# arduino_mini_can_bus.net
KiCad netlist of a schematic drawn in EAGLE
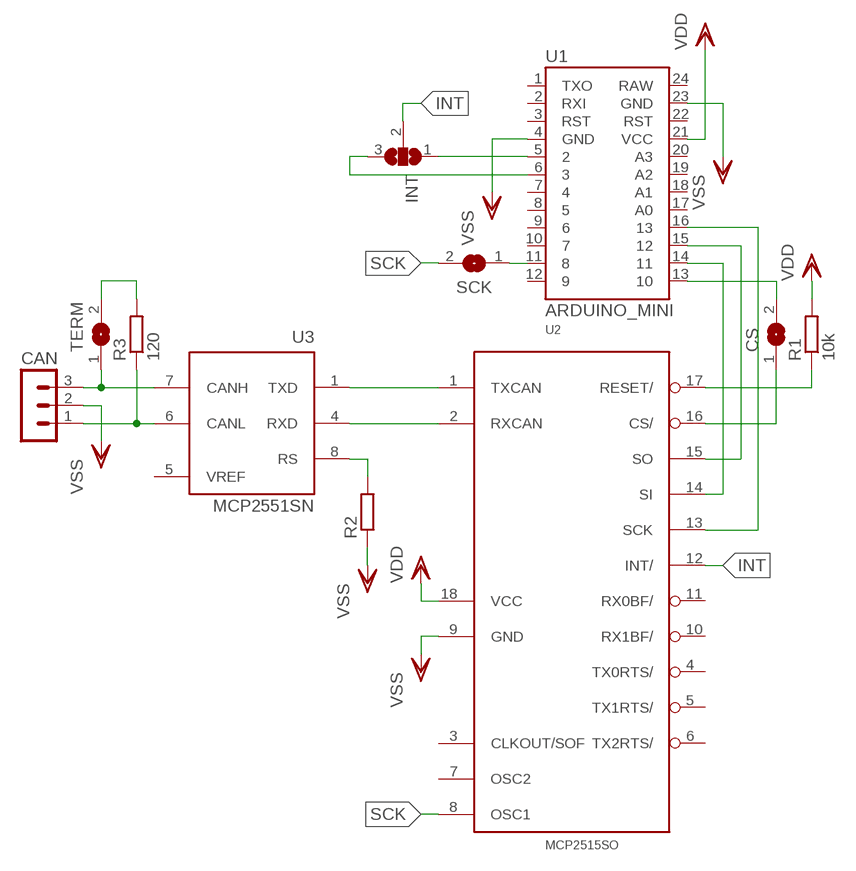
[diagram p0: schematic, sheet 1]

(export (version "E")
  (design (tool "Eeschema 10.0.6"))
  (components
    (comp (ref "CAN")
      (value "MA03-1")
      (footprint "eagle-import:MA03-1")
      (libsource (lib "eagle-import") (part "MA03-1"))
    )
    (comp (ref "CS") (value "SJ") (footprint "eagle-import:SJ") (libsource (lib "eagle-import") (part "SJ")))
    (comp (ref "INT")
      (value "SJ2W")
      (footprint "eagle-import:SJ_2")
      (libsource (lib "eagle-import") (part "SJ2W"))
    )
    (comp (ref "R1")
      (value "10k")
      (footprint "eagle-import:0207_10")
      (libsource (lib "eagle-import") (part "R-EU_0207/10"))
    )
    (comp (ref "R2")
      (value "R-EU_0207/10")
      (footprint "eagle-import:0207_10")
      (libsource (lib "eagle-import") (part "R-EU_0207/10"))
    )
    (comp (ref "R3")
      (value "120")
      (footprint "eagle-import:0207_10")
      (libsource (lib "eagle-import") (part "R-EU_0207/10"))
    )
    (comp (ref "SCK") (value "SJ") (footprint "eagle-import:SJ") (libsource (lib "eagle-import") (part "SJ")))
    (comp (ref "TERM")
      (value "SJ")
      (footprint "eagle-import:SJ")
      (libsource (lib "eagle-import") (part "SJ"))
    )
    (comp (ref "U1")
      (value "ARDUINO_MINI")
      (footprint "eagle-import:ARDUINO_MINI")
      (libsource (lib "eagle-import") (part "ARDUINO_MINI"))
    )
    (comp (ref "U2")
      (value "MCP2515SO")
      (footprint "eagle-import:SO18L")
      (libsource (lib "eagle-import") (part "MCP2515SO"))
    )
    (comp (ref "U3")
      (value "MCP2551SN")
      (footprint "eagle-import:SO-08")
      (libsource (lib "eagle-import") (part "MCP2551SN"))
    )
  )
  (nets
    (net (code "1") (name "/VREF") (class "Default")
      (node (ref "U3") (pin "5") (pinfunction "VREF_5") (pintype "power_in"))
    )
    (net (code "2") (name "INT") (class "Default")
      (node (ref "INT") (pin "2") (pinfunction "2_2") (pintype "passive"))
      (node (ref "U2") (pin "12") (pinfunction "INT/_12") (pintype "output"))
    )
    (net (code "3") (name "Net-(R3-Pad2)") (class "Default")
      (node (ref "R3") (pin "2") (pinfunction "2_2") (pintype "passive"))
      (node (ref "TERM") (pin "2") (pinfunction "2_2") (pintype "passive"))
    )
    (net (code "4") (name "Net-(U1-2)") (class "Default")
      (node (ref "INT") (pin "1") (pinfunction "1_1") (pintype "passive"))
      (node (ref "U1") (pin "5") (pinfunction "2_5") (pintype "bidirectional"))
    )
    (net (code "5") (name "Net-(U1-3)") (class "Default")
      (node (ref "INT") (pin "3") (pinfunction "3_3") (pintype "passive"))
      (node (ref "U1") (pin "6") (pinfunction "3_6") (pintype "bidirectional"))
    )
    (net (code "6") (name "Net-(U1-8)") (class "Default")
      (node (ref "SCK") (pin "1") (pinfunction "1_1") (pintype "passive"))
      (node (ref "U1") (pin "11") (pinfunction "8_11") (pintype "bidirectional"))
    )
    (net (code "7") (name "Net-(U1-10)") (class "Default")
      (node (ref "CS") (pin "2") (pinfunction "2_2") (pintype "passive"))
      (node (ref "U1") (pin "13") (pinfunction "10_13") (pintype "bidirectional"))
    )
    (net (code "8") (name "Net-(U1-11)") (class "Default")
      (node (ref "U1") (pin "14") (pinfunction "11_14") (pintype "bidirectional"))
      (node (ref "U2") (pin "14") (pinfunction "SI_14") (pintype "input"))
    )
    (net (code "9") (name "Net-(U1-12)") (class "Default")
      (node (ref "U1") (pin "15") (pinfunction "12_15") (pintype "bidirectional"))
      (node (ref "U2") (pin "15") (pinfunction "SO_15") (pintype "output"))
    )
    (net (code "10") (name "Net-(U1-13)") (class "Default")
      (node (ref "U1") (pin "16") (pinfunction "13_16") (pintype "bidirectional"))
      (node (ref "U2") (pin "13") (pinfunction "SCK_13") (pintype "input"))
    )
    (net (code "11") (name "Net-(U2-CS{slash})") (class "Default")
      (node (ref "CS") (pin "1") (pinfunction "1_1") (pintype "passive"))
      (node (ref "U2") (pin "16") (pinfunction "CS/_16") (pintype "input"))
    )
    (net (code "12") (name "Net-(U2-RESET{slash})") (class "Default")
      (node (ref "R1") (pin "1") (pinfunction "1_1") (pintype "passive"))
      (node (ref "U2") (pin "17") (pinfunction "RESET/_17") (pintype "input"))
    )
    (net (code "13") (name "Net-(U2-RXCAN)") (class "Default")
      (node (ref "U2") (pin "2") (pinfunction "RXCAN_2") (pintype "input"))
      (node (ref "U3") (pin "4") (pinfunction "RXD_4") (pintype "output"))
    )
    (net (code "14") (name "Net-(U2-TXCAN)") (class "Default")
      (node (ref "U2") (pin "1") (pinfunction "TXCAN_1") (pintype "output"))
      (node (ref "U3") (pin "1") (pinfunction "TXD_1") (pintype "input"))
    )
    (net (code "15") (name "Net-(U3A-CANH)") (class "Default")
      (node (ref "CAN") (pin "3") (pinfunction "3_3") (pintype "passive"))
      (node (ref "TERM") (pin "1") (pinfunction "1_1") (pintype "passive"))
      (node (ref "U3") (pin "7") (pinfunction "CANH_7") (pintype "bidirectional"))
    )
    (net (code "16") (name "Net-(U3A-CANL)") (class "Default")
      (node (ref "CAN") (pin "1") (pinfunction "1_1") (pintype "passive"))
      (node (ref "R3") (pin "1") (pinfunction "1_1") (pintype "passive"))
      (node (ref "U3") (pin "6") (pinfunction "CANL_6") (pintype "bidirectional"))
    )
    (net (code "17") (name "Net-(U3A-RS)") (class "Default")
      (node (ref "R2") (pin "2") (pinfunction "2_2") (pintype "passive"))
      (node (ref "U3") (pin "8") (pinfunction "RS_8") (pintype "input"))
    )
    (net (code "18") (name "SCK") (class "Default")
      (node (ref "SCK") (pin "2") (pinfunction "2_2") (pintype "passive"))
      (node (ref "U2") (pin "8") (pinfunction "OSC1_8") (pintype "bidirectional"))
    )
    (net (code "19") (name "VDD") (class "Default")
      (node (ref "R1") (pin "2") (pinfunction "2_2") (pintype "passive"))
      (node (ref "U1") (pin "21") (pinfunction "VCC_21") (pintype "bidirectional"))
      (node (ref "U2") (pin "18") (pinfunction "VCC_18") (pintype "power_in"))
    )
    (net (code "20") (name "VSS") (class "Default")
      (node (ref "CAN") (pin "2") (pinfunction "2_2") (pintype "passive"))
      (node (ref "R2") (pin "1") (pinfunction "1_1") (pintype "passive"))
      (node (ref "U1") (pin "23") (pinfunction "GND_23") (pintype "bidirectional"))
      (node (ref "U1") (pin "4") (pinfunction "GND_4") (pintype "bidirectional"))
      (node (ref "U2") (pin "9") (pinfunction "GND_9") (pintype "power_in"))
    )
    (net (code "21") (name "unconnected-(U1-4-Pad7)") (class "Default")
      (node (ref "U1") (pin "7") (pinfunction "4_7") (pintype "bidirectional"))
    )
    (net (code "22") (name "unconnected-(U1-5-Pad8)") (class "Default")
      (node (ref "U1") (pin "8") (pinfunction "5_8") (pintype "bidirectional"))
    )
    (net (code "23") (name "unconnected-(U1-6-Pad9)") (class "Default")
      (node (ref "U1") (pin "9") (pinfunction "6_9") (pintype "bidirectional"))
    )
    (net (code "24") (name "unconnected-(U1-7-Pad10)") (class "Default")
      (node (ref "U1") (pin "10") (pinfunction "7_10") (pintype "bidirectional"))
    )
    (net (code "25") (name "unconnected-(U1-9-Pad12)") (class "Default")
      (node (ref "U1") (pin "12") (pinfunction "9_12") (pintype "bidirectional"))
    )
    (net (code "26") (name "unconnected-(U1-A0-Pad17)") (class "Default")
      (node (ref "U1") (pin "17") (pinfunction "A0_17") (pintype "bidirectional"))
    )
    (net (code "27") (name "unconnected-(U1-A1-Pad18)") (class "Default")
      (node (ref "U1") (pin "18") (pinfunction "A1_18") (pintype "bidirectional"))
    )
    (net (code "28") (name "unconnected-(U1-A2-Pad19)") (class "Default")
      (node (ref "U1") (pin "19") (pinfunction "A2_19") (pintype "bidirectional"))
    )
    (net (code "29") (name "unconnected-(U1-A3-Pad20)") (class "Default")
      (node (ref "U1") (pin "20") (pinfunction "A3_20") (pintype "bidirectional"))
    )
    (net (code "30") (name "unconnected-(U1-RAW-Pad24)") (class "Default")
      (node (ref "U1") (pin "24") (pinfunction "RAW_24") (pintype "bidirectional"))
    )
    (net (code "31") (name "unconnected-(U1-RST-Pad3)") (class "Default")
      (node (ref "U1") (pin "3") (pinfunction "RST_3") (pintype "bidirectional"))
    )
    (net (code "32") (name "unconnected-(U1-RST-Pad22)") (class "Default")
      (node (ref "U1") (pin "22") (pinfunction "RST_22") (pintype "bidirectional"))
    )
    (net (code "33") (name "unconnected-(U1-RXI-Pad2)") (class "Default")
      (node (ref "U1") (pin "2") (pinfunction "RXI_2") (pintype "bidirectional"))
    )
    (net (code "34") (name "unconnected-(U1-TXO-Pad1)") (class "Default")
      (node (ref "U1") (pin "1") (pinfunction "TXO_1") (pintype "bidirectional"))
    )
    (net (code "35") (name "unconnected-(U2-CLKOUT{slash}SOF-Pad3)") (class "Default")
      (node (ref "U2") (pin "3") (pinfunction "CLKOUT/SOF_3") (pintype "bidirectional"))
    )
    (net (code "36") (name "unconnected-(U2-OSC2-Pad7)") (class "Default")
      (node (ref "U2") (pin "7") (pinfunction "OSC2_7") (pintype "bidirectional"))
    )
    (net (code "37") (name "unconnected-(U2-RX0BF{slash}-Pad11)") (class "Default")
      (node (ref "U2") (pin "11") (pinfunction "RX0BF/_11") (pintype "bidirectional"))
    )
    (net (code "38") (name "unconnected-(U2-RX1BF{slash}-Pad10)") (class "Default")
      (node (ref "U2") (pin "10") (pinfunction "RX1BF/_10") (pintype "bidirectional"))
    )
    (net (code "39") (name "unconnected-(U2-TX0RTS{slash}-Pad4)") (class "Default")
      (node (ref "U2") (pin "4") (pinfunction "TX0RTS/_4") (pintype "bidirectional"))
    )
    (net (code "40") (name "unconnected-(U2-TX1RTS{slash}-Pad5)") (class "Default")
      (node (ref "U2") (pin "5") (pinfunction "TX1RTS/_5") (pintype "bidirectional"))
    )
    (net (code "41") (name "unconnected-(U2-TX2RTS{slash}-Pad6)") (class "Default")
      (node (ref "U2") (pin "6") (pinfunction "TX2RTS/_6") (pintype "bidirectional"))
    )
  )
)
